# 12_ADAU7118_CODEC.net
KiCad netlist of a schematic drawn in Altium Designer
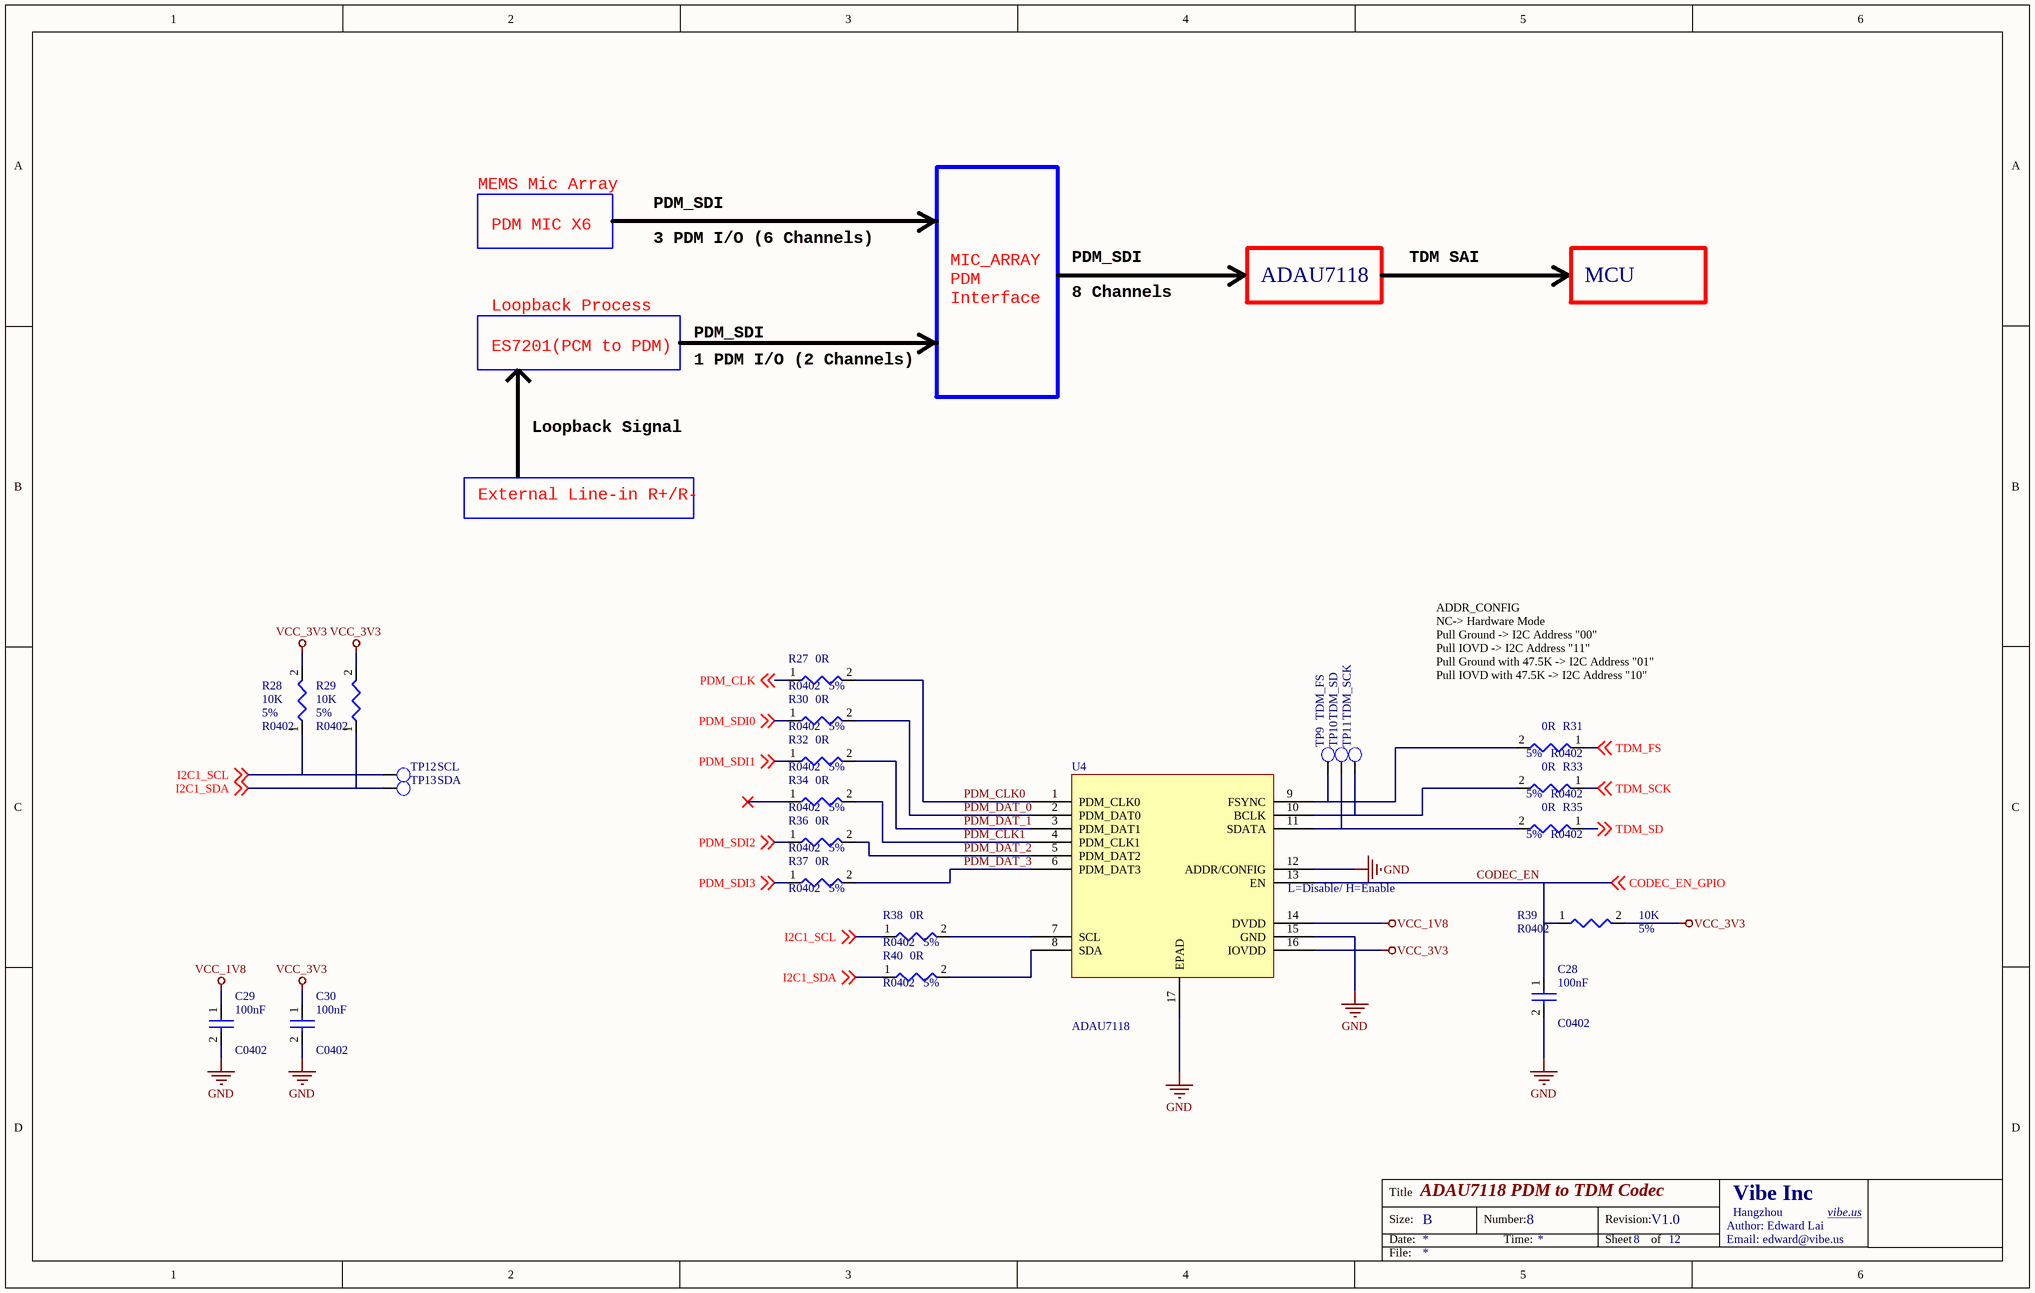
[diagram p0: 12_ADAU7118_CODEC.SchDoc]

(export (version "E")
  (design (tool "Eeschema 10.0.6"))
  (components
    (comp (ref "C28")
      (value "100nF")
      (footprint "C0402_L")
      (description "cap,1.0uF,+/-10%,6.3V,C0402")
      (fields (field (name "PCB FOOTPRINT") "C0402"))
      (libsource (lib "*") (part "CAP NP_Dup1"))
    )
    (comp (ref "C29")
      (value "100nF")
      (footprint "C0402_L")
      (description "cap,1.0uF,+/-10%,6.3V,C0402")
      (fields (field (name "PCB FOOTPRINT") "C0402"))
      (libsource (lib "*") (part "CAP NP_Dup1"))
    )
    (comp (ref "C30")
      (value "100nF")
      (footprint "C0402_L")
      (description "cap,1.0uF,+/-10%,6.3V,C0402")
      (fields (field (name "PCB FOOTPRINT") "C0402"))
      (libsource (lib "*") (part "CAP NP_Dup1"))
    )
    (comp (ref "R27")
      (value "0R")
      (footprint "R0402")
      (description "通用厚膜电阻,0R,+/-5%,R0402")
      (fields (field (name "PCB FOOTPRINT") "R0402") (field (name "TOLERANCE") "5%"))
      (libsource (lib "*") (part "RESISTOR"))
    )
    (comp (ref "R28")
      (value "10K")
      (footprint "R0402")
      (description "通用厚膜电阻,10K,+/-5%,R0402")
      (fields (field (name "PCB FOOTPRINT") "R0402") (field (name "TOLERANCE") "5%"))
      (libsource (lib "*") (part "RESISTOR"))
    )
    (comp (ref "R29")
      (value "10K")
      (footprint "R0402")
      (description "通用厚膜电阻,10K,+/-5%,R0402")
      (fields (field (name "PCB FOOTPRINT") "R0402") (field (name "TOLERANCE") "5%"))
      (libsource (lib "*") (part "RESISTOR"))
    )
    (comp (ref "R30")
      (value "0R")
      (footprint "R0402")
      (description "通用厚膜电阻,0R,+/-5%,R0402")
      (fields (field (name "PCB FOOTPRINT") "R0402") (field (name "TOLERANCE") "5%"))
      (libsource (lib "*") (part "RESISTOR"))
    )
    (comp (ref "R31")
      (value "0R")
      (footprint "R0402")
      (description "通用厚膜电阻,0R,+/-5%,R0402")
      (fields (field (name "PCB FOOTPRINT") "R0402") (field (name "TOLERANCE") "5%"))
      (libsource (lib "*") (part "RESISTOR"))
    )
    (comp (ref "R32")
      (value "0R")
      (footprint "R0402")
      (description "通用厚膜电阻,0R,+/-5%,R0402")
      (fields (field (name "PCB FOOTPRINT") "R0402") (field (name "TOLERANCE") "5%"))
      (libsource (lib "*") (part "RESISTOR"))
    )
    (comp (ref "R33")
      (value "0R")
      (footprint "R0402")
      (description "通用厚膜电阻,0R,+/-5%,R0402")
      (fields (field (name "PCB FOOTPRINT") "R0402") (field (name "TOLERANCE") "5%"))
      (libsource (lib "*") (part "RESISTOR"))
    )
    (comp (ref "R34")
      (value "0R")
      (footprint "R0402")
      (description "通用厚膜电阻,0R,+/-5%,R0402")
      (fields (field (name "PCB FOOTPRINT") "R0402") (field (name "TOLERANCE") "5%"))
      (libsource (lib "*") (part "RESISTOR"))
    )
    (comp (ref "R35")
      (value "0R")
      (footprint "R0402")
      (description "通用厚膜电阻,0R,+/-5%,R0402")
      (fields (field (name "PCB FOOTPRINT") "R0402") (field (name "TOLERANCE") "5%"))
      (libsource (lib "*") (part "RESISTOR"))
    )
    (comp (ref "R36")
      (value "0R")
      (footprint "R0402")
      (description "通用厚膜电阻,0R,+/-5%,R0402")
      (fields (field (name "PCB FOOTPRINT") "R0402") (field (name "TOLERANCE") "5%"))
      (libsource (lib "*") (part "RESISTOR"))
    )
    (comp (ref "R37")
      (value "0R")
      (footprint "R0402")
      (description "通用厚膜电阻,0R,+/-5%,R0402")
      (fields (field (name "PCB FOOTPRINT") "R0402") (field (name "TOLERANCE") "5%"))
      (libsource (lib "*") (part "RESISTOR"))
    )
    (comp (ref "R38")
      (value "0R")
      (footprint "R0402")
      (description "通用厚膜电阻,0R,+/-5%,R0402")
      (fields (field (name "PCB FOOTPRINT") "R0402") (field (name "TOLERANCE") "5%"))
      (libsource (lib "*") (part "RESISTOR"))
    )
    (comp (ref "R39")
      (value "10K")
      (footprint "R0402")
      (description "通用厚膜电阻,10K,+/-5%,R0402")
      (fields (field (name "PCB FOOTPRINT") "R0402") (field (name "TOLERANCE") "5%"))
      (libsource (lib "*") (part "RESISTOR"))
    )
    (comp (ref "R40")
      (value "0R")
      (footprint "R0402")
      (description "通用厚膜电阻,0R,+/-5%,R0402")
      (fields (field (name "PCB FOOTPRINT") "R0402") (field (name "TOLERANCE") "5%"))
      (libsource (lib "*") (part "RESISTOR"))
    )
    (comp (ref "TP9")
      (value "TDM_FS")
      (footprint "TP_0R70")
      (description "Test Point 0.7mm")
      (libsource (lib "Schlib1") (part "TP"))
    )
    (comp (ref "TP10")
      (value "TDM_SD")
      (footprint "TP_0R70")
      (description "Test Point 0.7mm")
      (libsource (lib "Schlib1") (part "TP"))
    )
    (comp (ref "TP11")
      (value "TDM_SCK")
      (footprint "TP_0R70")
      (description "Test Point 0.7mm")
      (libsource (lib "Schlib1") (part "TP"))
    )
    (comp (ref "TP12")
      (value "SCL")
      (footprint "TP_0R70")
      (description "Test Point 0.7mm")
      (libsource (lib "Schlib1") (part "TP"))
    )
    (comp (ref "TP13")
      (value "SDA")
      (footprint "TP_0R70")
      (description "Test Point 0.7mm")
      (libsource (lib "Schlib1") (part "TP"))
    )
    (comp (ref "U4")
      (value "ADAU7118")
      (footprint "QFN50P300X300X80-17N")
      (description "16-lead, 3 mm × 3 mm, 0.50 mm pitch LFCSP")
      (libsource (lib "Schlib1") (part "ADAU7118"))
    )
  )
  (nets
    (net (code "1") (name "/PDM_CLK0") (class "Default")
      (node (ref "R27") (pin "2") (pinfunction "2_2") (pintype "passive"))
      (node (ref "U4") (pin "1") (pinfunction "PDM_CLK0_1") (pintype "passive"))
    )
    (net (code "2") (name "/PDM_CLK1") (class "Default")
      (node (ref "R34") (pin "2") (pinfunction "2_2") (pintype "passive"))
      (node (ref "U4") (pin "4") (pinfunction "PDM_CLK1_4") (pintype "passive"))
    )
    (net (code "3") (name "/PDM_DAT_0") (class "Default")
      (node (ref "R30") (pin "2") (pinfunction "2_2") (pintype "passive"))
      (node (ref "U4") (pin "2") (pinfunction "PDM_DAT0_2") (pintype "passive"))
    )
    (net (code "4") (name "/PDM_DAT_1") (class "Default")
      (node (ref "R32") (pin "2") (pinfunction "2_2") (pintype "passive"))
      (node (ref "U4") (pin "3") (pinfunction "PDM_DAT1_3") (pintype "passive"))
    )
    (net (code "5") (name "/PDM_DAT_2") (class "Default")
      (node (ref "R36") (pin "2") (pinfunction "2_2") (pintype "passive"))
      (node (ref "U4") (pin "5") (pinfunction "PDM_DAT2_5") (pintype "passive"))
    )
    (net (code "6") (name "/PDM_DAT_3") (class "Default")
      (node (ref "R37") (pin "2") (pinfunction "2_2") (pintype "passive"))
      (node (ref "U4") (pin "6") (pinfunction "PDM_DAT3_6") (pintype "passive"))
    )
    (net (code "7") (name "CODEC_EN_GPIO") (class "Default")
      (node (ref "C28") (pin "1") (pinfunction "1_1") (pintype "passive"))
      (node (ref "R39") (pin "1") (pinfunction "1_1") (pintype "passive"))
      (node (ref "U4") (pin "13") (pinfunction "EN_13") (pintype "passive"))
    )
    (net (code "8") (name "GND") (class "Default")
      (node (ref "C28") (pin "2") (pinfunction "2_2") (pintype "passive"))
      (node (ref "C29") (pin "2") (pinfunction "2_2") (pintype "passive"))
      (node (ref "C30") (pin "2") (pinfunction "2_2") (pintype "passive"))
      (node (ref "U4") (pin "12") (pinfunction "ADDR/CONFIG_12") (pintype "passive"))
      (node (ref "U4") (pin "15") (pinfunction "GND_15") (pintype "passive"))
      (node (ref "U4") (pin "17") (pinfunction "EPAD_17") (pintype "passive"))
    )
    (net (code "9") (name "I2C1_SCL") (class "Default")
      (node (ref "R28") (pin "1") (pinfunction "1_1") (pintype "passive"))
      (node (ref "R38") (pin "1") (pinfunction "1_1") (pintype "passive"))
      (node (ref "TP12") (pin "1") (pinfunction "1_1") (pintype "passive"))
    )
    (net (code "10") (name "I2C1_SDA") (class "Default")
      (node (ref "R29") (pin "1") (pinfunction "1_1") (pintype "passive"))
      (node (ref "R40") (pin "1") (pinfunction "1_1") (pintype "passive"))
      (node (ref "TP13") (pin "1") (pinfunction "1_1") (pintype "passive"))
    )
    (net (code "11") (name "Net-(U4-BCLK)") (class "Default")
      (node (ref "R33") (pin "2") (pinfunction "2_2") (pintype "passive"))
      (node (ref "TP11") (pin "1") (pinfunction "1_1") (pintype "passive"))
      (node (ref "U4") (pin "10") (pinfunction "BCLK_10") (pintype "passive"))
    )
    (net (code "12") (name "Net-(U4-FSYNC)") (class "Default")
      (node (ref "R31") (pin "2") (pinfunction "2_2") (pintype "passive"))
      (node (ref "TP9") (pin "1") (pinfunction "1_1") (pintype "passive"))
      (node (ref "U4") (pin "9") (pinfunction "FSYNC_9") (pintype "passive"))
    )
    (net (code "13") (name "Net-(U4-SCL)") (class "Default")
      (node (ref "R38") (pin "2") (pinfunction "2_2") (pintype "passive"))
      (node (ref "U4") (pin "7") (pinfunction "SCL_7") (pintype "passive"))
    )
    (net (code "14") (name "Net-(U4-SDA)") (class "Default")
      (node (ref "R40") (pin "2") (pinfunction "2_2") (pintype "passive"))
      (node (ref "U4") (pin "8") (pinfunction "SDA_8") (pintype "passive"))
    )
    (net (code "15") (name "Net-(U4-SDATA)") (class "Default")
      (node (ref "R35") (pin "2") (pinfunction "2_2") (pintype "passive"))
      (node (ref "TP10") (pin "1") (pinfunction "1_1") (pintype "passive"))
      (node (ref "U4") (pin "11") (pinfunction "SDATA_11") (pintype "passive"))
    )
    (net (code "16") (name "PDM_CLK") (class "Default")
      (node (ref "R27") (pin "1") (pinfunction "1_1") (pintype "passive"))
    )
    (net (code "17") (name "PDM_SDI0") (class "Default")
      (node (ref "R30") (pin "1") (pinfunction "1_1") (pintype "passive"))
    )
    (net (code "18") (name "PDM_SDI1") (class "Default")
      (node (ref "R32") (pin "1") (pinfunction "1_1") (pintype "passive"))
    )
    (net (code "19") (name "PDM_SDI2") (class "Default")
      (node (ref "R36") (pin "1") (pinfunction "1_1") (pintype "passive"))
    )
    (net (code "20") (name "PDM_SDI3") (class "Default")
      (node (ref "R37") (pin "1") (pinfunction "1_1") (pintype "passive"))
    )
    (net (code "21") (name "TDM_FS") (class "Default")
      (node (ref "R31") (pin "1") (pinfunction "1_1") (pintype "passive"))
    )
    (net (code "22") (name "TDM_SCK") (class "Default")
      (node (ref "R33") (pin "1") (pinfunction "1_1") (pintype "passive"))
    )
    (net (code "23") (name "TDM_SD") (class "Default")
      (node (ref "R35") (pin "1") (pinfunction "1_1") (pintype "passive"))
    )
    (net (code "24") (name "VCC_1V8") (class "Default")
      (node (ref "C29") (pin "1") (pinfunction "1_1") (pintype "passive"))
      (node (ref "U4") (pin "14") (pinfunction "DVDD_14") (pintype "passive"))
    )
    (net (code "25") (name "VCC_3V3") (class "Default")
      (node (ref "C30") (pin "1") (pinfunction "1_1") (pintype "passive"))
      (node (ref "R28") (pin "2") (pinfunction "2_2") (pintype "passive"))
      (node (ref "R29") (pin "2") (pinfunction "2_2") (pintype "passive"))
      (node (ref "R39") (pin "2") (pinfunction "2_2") (pintype "passive"))
      (node (ref "U4") (pin "16") (pinfunction "IOVDD_16") (pintype "passive"))
    )
    (net (code "26") (name "unconnected-(R34-Pad1)") (class "Default")
      (node (ref "R34") (pin "1") (pinfunction "1_1") (pintype "passive+no_connect"))
    )
  )
)
